# PF_Dolly_Shield4.net
KiCad netlist of a schematic drawn in EAGLE
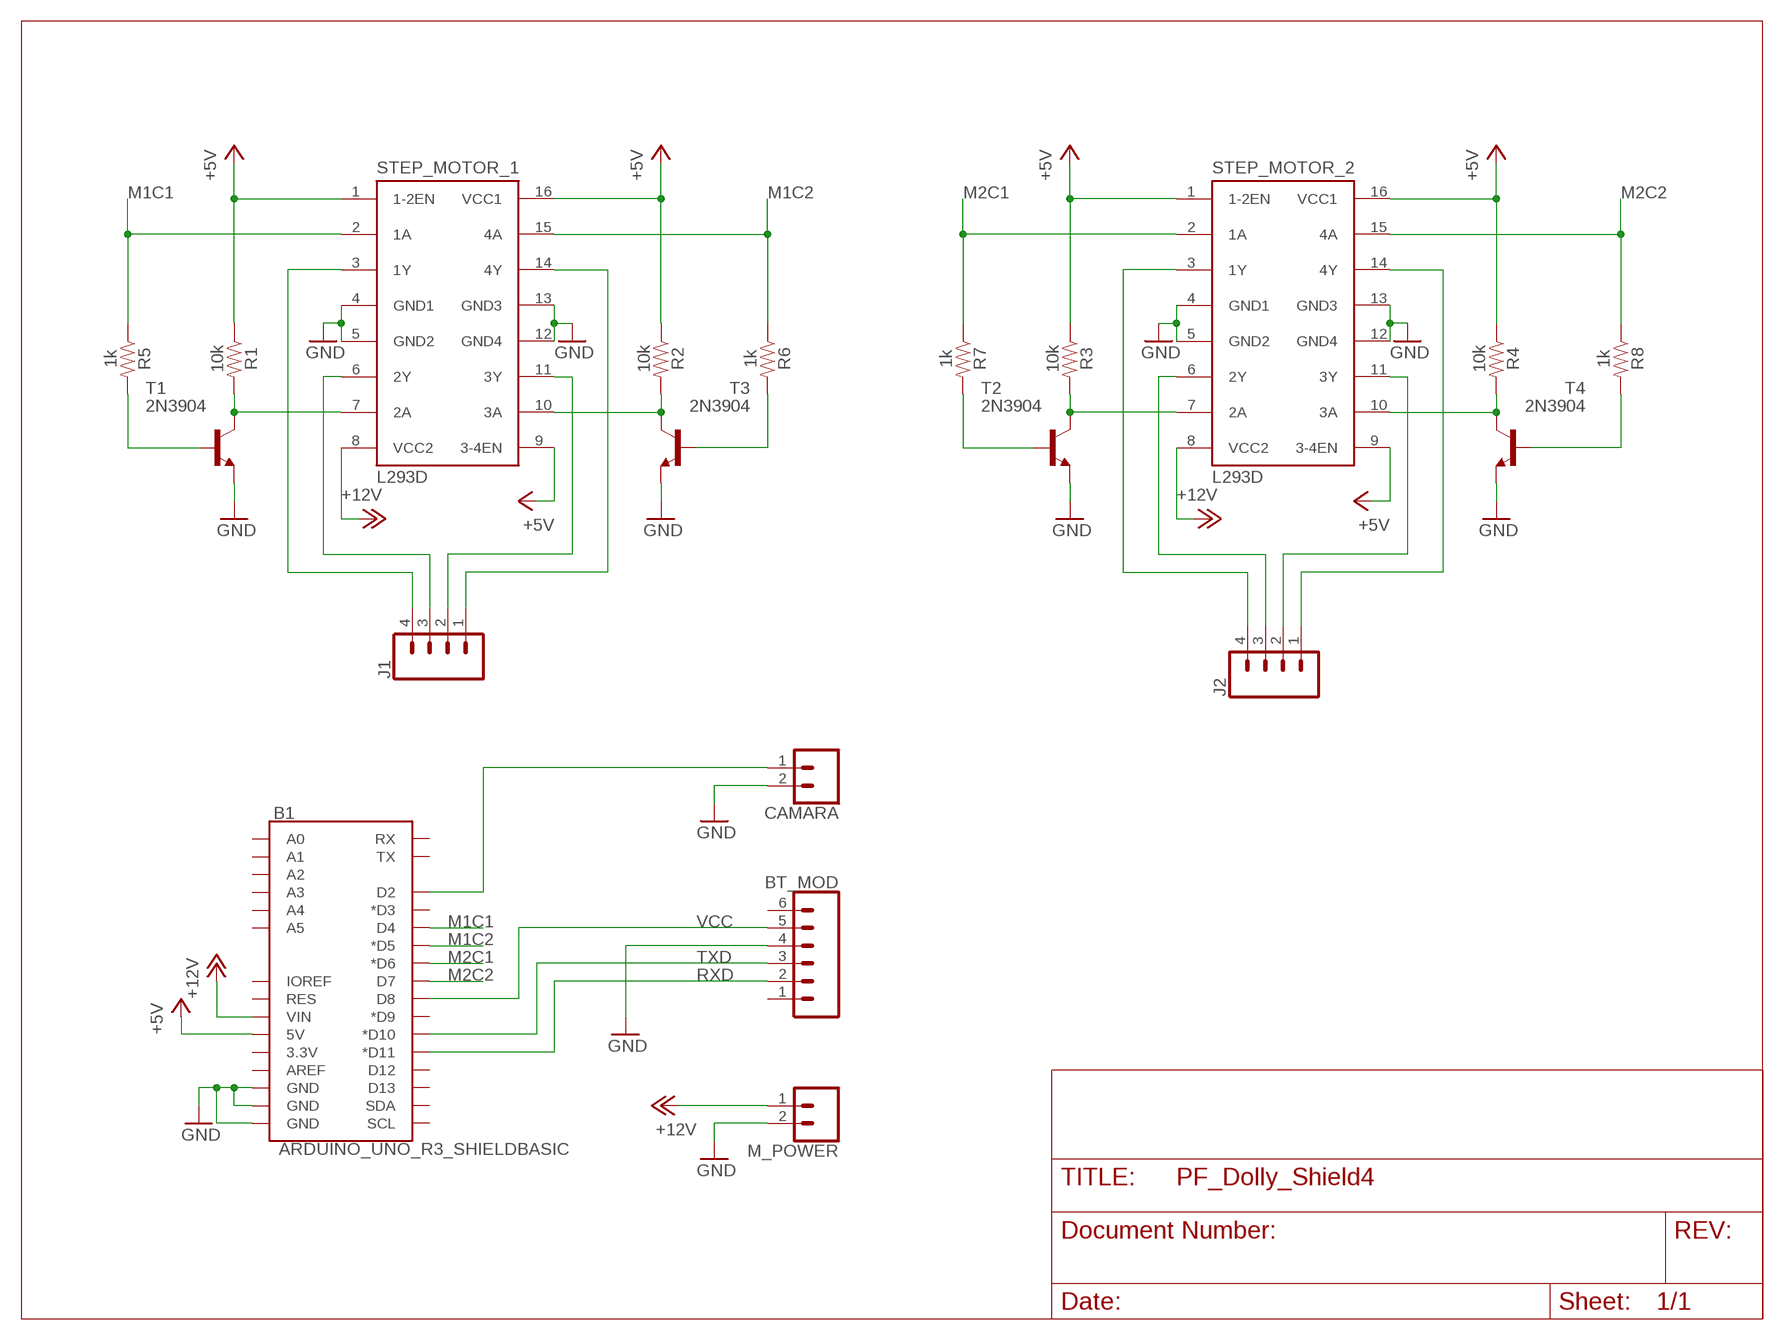
[diagram p0: schematic, sheet 1]

(export (version "E")
  (design (tool "Eeschema 10.0.6"))
  (components
    (comp (ref "B1")
      (value "ARDUINO_UNO_R3_SHIELDBASIC")
      (footprint "eagle-import:UNO_R3_SHIELD")
      (libsource (lib "eagle-import") (part "ARDUINO_UNO_R3_SHIELDBASIC"))
    )
    (comp (ref "BT_MOD")
      (value "CONN_06LONGPADS")
      (footprint "eagle-import:1X06_LONGPADS")
      (libsource (lib "eagle-import") (part "CONN_06LONGPADS"))
    )
    (comp (ref "CAMARA")
      (value "CONN_025MM")
      (footprint "eagle-import:SCREWTERMINAL-5MM-2")
      (libsource (lib "eagle-import") (part "CONN_025MM"))
    )
    (comp (ref "J1")
      (value "CONN_04POLAR")
      (footprint "eagle-import:MOLEX-1X4")
      (libsource (lib "eagle-import") (part "CONN_04POLAR"))
    )
    (comp (ref "J2")
      (value "CONN_04POLAR")
      (footprint "eagle-import:MOLEX-1X4")
      (libsource (lib "eagle-import") (part "CONN_04POLAR"))
    )
    (comp (ref "M_POWER")
      (value "CONN_025MM")
      (footprint "eagle-import:SCREWTERMINAL-5MM-2")
      (libsource (lib "eagle-import") (part "CONN_025MM"))
    )
    (comp (ref "R1")
      (value "10k")
      (footprint "eagle-import:AXIAL-0.3")
      (libsource (lib "eagle-import") (part "10KOHM-HORIZ-1/4W-5%"))
    )
    (comp (ref "R2")
      (value "10k")
      (footprint "eagle-import:AXIAL-0.3")
      (libsource (lib "eagle-import") (part "10KOHM-HORIZ-1/4W-5%"))
    )
    (comp (ref "R3")
      (value "10k")
      (footprint "eagle-import:AXIAL-0.3")
      (libsource (lib "eagle-import") (part "10KOHM-HORIZ-1/4W-5%"))
    )
    (comp (ref "R4")
      (value "10k")
      (footprint "eagle-import:AXIAL-0.3")
      (libsource (lib "eagle-import") (part "10KOHM-HORIZ-1/4W-5%"))
    )
    (comp (ref "R5")
      (value "1k")
      (footprint "eagle-import:AXIAL-0.3")
      (libsource (lib "eagle-import") (part "1KOHM-HORIZ-1/4W-5%"))
    )
    (comp (ref "R6")
      (value "1k")
      (footprint "eagle-import:AXIAL-0.3")
      (libsource (lib "eagle-import") (part "1KOHM-HORIZ-1/4W-5%"))
    )
    (comp (ref "R7")
      (value "1k")
      (footprint "eagle-import:AXIAL-0.3")
      (libsource (lib "eagle-import") (part "1KOHM-HORIZ-1/4W-5%"))
    )
    (comp (ref "R8")
      (value "1k")
      (footprint "eagle-import:AXIAL-0.3")
      (libsource (lib "eagle-import") (part "1KOHM-HORIZ-1/4W-5%"))
    )
    (comp (ref "STEP_MOTOR_1")
      (value "L293D")
      (footprint "eagle-import:DIL16")
      (libsource (lib "eagle-import") (part "L293D"))
    )
    (comp (ref "STEP_MOTOR_2")
      (value "L293D")
      (footprint "eagle-import:DIL16")
      (libsource (lib "eagle-import") (part "L293D"))
    )
    (comp (ref "T1")
      (value "2N3904")
      (footprint "eagle-import:TO92")
      (libsource (lib "eagle-import") (part "2N3904"))
    )
    (comp (ref "T2")
      (value "2N3904")
      (footprint "eagle-import:TO92")
      (libsource (lib "eagle-import") (part "2N3904"))
    )
    (comp (ref "T3")
      (value "2N3904")
      (footprint "eagle-import:TO92")
      (libsource (lib "eagle-import") (part "2N3904"))
    )
    (comp (ref "T4")
      (value "2N3904")
      (footprint "eagle-import:TO92")
      (libsource (lib "eagle-import") (part "2N3904"))
    )
  )
  (nets
    (net (code "1") (name "+5V") (class "Default")
      (node (ref "B1") (pin "5V") (pinfunction "5V_5V") (pintype "bidirectional"))
      (node (ref "R1") (pin "P$1") (pinfunction "1_P$1") (pintype "passive"))
      (node (ref "R2") (pin "P$1") (pinfunction "1_P$1") (pintype "passive"))
      (node (ref "R3") (pin "P$1") (pinfunction "1_P$1") (pintype "passive"))
      (node (ref "R4") (pin "P$1") (pinfunction "1_P$1") (pintype "passive"))
      (node (ref "STEP_MOTOR_1") (pin "1") (pinfunction "1-2EN_1") (pintype "input"))
      (node (ref "STEP_MOTOR_1") (pin "16") (pinfunction "VCC1_16") (pintype "power_in"))
      (node (ref "STEP_MOTOR_1") (pin "9") (pinfunction "3-4EN_9") (pintype "input"))
      (node (ref "STEP_MOTOR_2") (pin "1") (pinfunction "1-2EN_1") (pintype "input"))
      (node (ref "STEP_MOTOR_2") (pin "16") (pinfunction "VCC1_16") (pintype "power_in"))
      (node (ref "STEP_MOTOR_2") (pin "9") (pinfunction "3-4EN_9") (pintype "input"))
    )
    (net (code "2") (name "+12V") (class "Default")
      (node (ref "B1") (pin "VIN") (pinfunction "VIN_VIN") (pintype "bidirectional"))
      (node (ref "M_POWER") (pin "1") (pinfunction "1_1") (pintype "passive"))
      (node (ref "STEP_MOTOR_1") (pin "8") (pinfunction "VCC2_8") (pintype "power_in"))
      (node (ref "STEP_MOTOR_2") (pin "8") (pinfunction "VCC2_8") (pintype "power_in"))
    )
    (net (code "3") (name "/M1C1") (class "Default")
      (node (ref "B1") (pin "D4") (pinfunction "D4_D4") (pintype "bidirectional"))
      (node (ref "R5") (pin "P$1") (pinfunction "1_P$1") (pintype "passive"))
      (node (ref "STEP_MOTOR_1") (pin "2") (pinfunction "1A_2") (pintype "input"))
    )
    (net (code "4") (name "/M1C2") (class "Default")
      (node (ref "B1") (pin "D5") (pinfunction "*D5_D5") (pintype "bidirectional"))
      (node (ref "R6") (pin "P$1") (pinfunction "1_P$1") (pintype "passive"))
      (node (ref "STEP_MOTOR_1") (pin "15") (pinfunction "4A_15") (pintype "input"))
    )
    (net (code "5") (name "/M2C1") (class "Default")
      (node (ref "B1") (pin "D6") (pinfunction "*D6_D6") (pintype "bidirectional"))
      (node (ref "R7") (pin "P$1") (pinfunction "1_P$1") (pintype "passive"))
      (node (ref "STEP_MOTOR_2") (pin "2") (pinfunction "1A_2") (pintype "input"))
    )
    (net (code "6") (name "/M2C2") (class "Default")
      (node (ref "B1") (pin "D7") (pinfunction "D7_D7") (pintype "bidirectional"))
      (node (ref "R8") (pin "P$1") (pinfunction "1_P$1") (pintype "passive"))
      (node (ref "STEP_MOTOR_2") (pin "15") (pinfunction "4A_15") (pintype "input"))
    )
    (net (code "7") (name "/RXD") (class "Default")
      (node (ref "B1") (pin "D11") (pinfunction "*D11_D11") (pintype "bidirectional"))
      (node (ref "BT_MOD") (pin "2") (pinfunction "2_2") (pintype "passive"))
    )
    (net (code "8") (name "/TXD") (class "Default")
      (node (ref "B1") (pin "D10") (pinfunction "*D10_D10") (pintype "bidirectional"))
      (node (ref "BT_MOD") (pin "3") (pinfunction "3_3") (pintype "passive"))
    )
    (net (code "9") (name "/VCC") (class "Default")
      (node (ref "B1") (pin "D8") (pinfunction "D8_D8") (pintype "bidirectional"))
      (node (ref "BT_MOD") (pin "5") (pinfunction "5_5") (pintype "passive"))
    )
    (net (code "10") (name "GND") (class "Default")
      (node (ref "B1") (pin "GND@0") (pinfunction "GND_GND@0") (pintype "bidirectional"))
      (node (ref "B1") (pin "GND@1") (pinfunction "GND_GND@1") (pintype "bidirectional"))
      (node (ref "B1") (pin "GND@2") (pinfunction "GND_GND@2") (pintype "bidirectional"))
      (node (ref "BT_MOD") (pin "4") (pinfunction "4_4") (pintype "passive"))
      (node (ref "CAMARA") (pin "2") (pinfunction "2_2") (pintype "passive"))
      (node (ref "M_POWER") (pin "2") (pinfunction "2_2") (pintype "passive"))
      (node (ref "STEP_MOTOR_1") (pin "12") (pinfunction "GND4_12") (pintype "power_in"))
      (node (ref "STEP_MOTOR_1") (pin "13") (pinfunction "GND3_13") (pintype "power_in"))
      (node (ref "STEP_MOTOR_1") (pin "4") (pinfunction "GND1_4") (pintype "power_in"))
      (node (ref "STEP_MOTOR_1") (pin "5") (pinfunction "GND2_5") (pintype "power_in"))
      (node (ref "STEP_MOTOR_2") (pin "12") (pinfunction "GND4_12") (pintype "power_in"))
      (node (ref "STEP_MOTOR_2") (pin "13") (pinfunction "GND3_13") (pintype "power_in"))
      (node (ref "STEP_MOTOR_2") (pin "4") (pinfunction "GND1_4") (pintype "power_in"))
      (node (ref "STEP_MOTOR_2") (pin "5") (pinfunction "GND2_5") (pintype "power_in"))
      (node (ref "T1") (pin "3") (pinfunction "E_3") (pintype "passive"))
      (node (ref "T2") (pin "3") (pinfunction "E_3") (pintype "passive"))
      (node (ref "T3") (pin "3") (pinfunction "E_3") (pintype "passive"))
      (node (ref "T4") (pin "3") (pinfunction "E_3") (pintype "passive"))
    )
    (net (code "11") (name "Net-(B1-PadD2)") (class "Default")
      (node (ref "B1") (pin "D2") (pinfunction "D2_D2") (pintype "bidirectional"))
      (node (ref "CAMARA") (pin "1") (pinfunction "1_1") (pintype "passive"))
    )
    (net (code "12") (name "Net-(R1-2)") (class "Default")
      (node (ref "R1") (pin "P$2") (pinfunction "2_P$2") (pintype "passive"))
      (node (ref "STEP_MOTOR_1") (pin "7") (pinfunction "2A_7") (pintype "input"))
      (node (ref "T1") (pin "1") (pinfunction "C_1") (pintype "passive"))
    )
    (net (code "13") (name "Net-(R2-2)") (class "Default")
      (node (ref "R2") (pin "P$2") (pinfunction "2_P$2") (pintype "passive"))
      (node (ref "STEP_MOTOR_1") (pin "10") (pinfunction "3A_10") (pintype "input"))
      (node (ref "T3") (pin "1") (pinfunction "C_1") (pintype "passive"))
    )
    (net (code "14") (name "Net-(R3-2)") (class "Default")
      (node (ref "R3") (pin "P$2") (pinfunction "2_P$2") (pintype "passive"))
      (node (ref "STEP_MOTOR_2") (pin "7") (pinfunction "2A_7") (pintype "input"))
      (node (ref "T2") (pin "1") (pinfunction "C_1") (pintype "passive"))
    )
    (net (code "15") (name "Net-(R4-2)") (class "Default")
      (node (ref "R4") (pin "P$2") (pinfunction "2_P$2") (pintype "passive"))
      (node (ref "STEP_MOTOR_2") (pin "10") (pinfunction "3A_10") (pintype "input"))
      (node (ref "T4") (pin "1") (pinfunction "C_1") (pintype "passive"))
    )
    (net (code "16") (name "Net-(R5-2)") (class "Default")
      (node (ref "R5") (pin "P$2") (pinfunction "2_P$2") (pintype "passive"))
      (node (ref "T1") (pin "2") (pinfunction "B_2") (pintype "passive"))
    )
    (net (code "17") (name "Net-(R6-2)") (class "Default")
      (node (ref "R6") (pin "P$2") (pinfunction "2_P$2") (pintype "passive"))
      (node (ref "T3") (pin "2") (pinfunction "B_2") (pintype "passive"))
    )
    (net (code "18") (name "Net-(R7-2)") (class "Default")
      (node (ref "R7") (pin "P$2") (pinfunction "2_P$2") (pintype "passive"))
      (node (ref "T2") (pin "2") (pinfunction "B_2") (pintype "passive"))
    )
    (net (code "19") (name "Net-(R8-2)") (class "Default")
      (node (ref "R8") (pin "P$2") (pinfunction "2_P$2") (pintype "passive"))
      (node (ref "T4") (pin "2") (pinfunction "B_2") (pintype "passive"))
    )
    (net (code "20") (name "Net-(STEP_MOTOR_1-1Y)") (class "Default")
      (node (ref "J1") (pin "4") (pinfunction "4_4") (pintype "passive"))
      (node (ref "STEP_MOTOR_1") (pin "3") (pinfunction "1Y_3") (pintype "output"))
    )
    (net (code "21") (name "Net-(STEP_MOTOR_1-2Y)") (class "Default")
      (node (ref "J1") (pin "3") (pinfunction "3_3") (pintype "passive"))
      (node (ref "STEP_MOTOR_1") (pin "6") (pinfunction "2Y_6") (pintype "output"))
    )
    (net (code "22") (name "Net-(STEP_MOTOR_1-3Y)") (class "Default")
      (node (ref "J1") (pin "2") (pinfunction "2_2") (pintype "passive"))
      (node (ref "STEP_MOTOR_1") (pin "11") (pinfunction "3Y_11") (pintype "output"))
    )
    (net (code "23") (name "Net-(STEP_MOTOR_1-4Y)") (class "Default")
      (node (ref "J1") (pin "1") (pinfunction "1_1") (pintype "passive"))
      (node (ref "STEP_MOTOR_1") (pin "14") (pinfunction "4Y_14") (pintype "output"))
    )
    (net (code "24") (name "Net-(STEP_MOTOR_2-1Y)") (class "Default")
      (node (ref "J2") (pin "4") (pinfunction "4_4") (pintype "passive"))
      (node (ref "STEP_MOTOR_2") (pin "3") (pinfunction "1Y_3") (pintype "output"))
    )
    (net (code "25") (name "Net-(STEP_MOTOR_2-2Y)") (class "Default")
      (node (ref "J2") (pin "3") (pinfunction "3_3") (pintype "passive"))
      (node (ref "STEP_MOTOR_2") (pin "6") (pinfunction "2Y_6") (pintype "output"))
    )
    (net (code "26") (name "Net-(STEP_MOTOR_2-3Y)") (class "Default")
      (node (ref "J2") (pin "2") (pinfunction "2_2") (pintype "passive"))
      (node (ref "STEP_MOTOR_2") (pin "11") (pinfunction "3Y_11") (pintype "output"))
    )
    (net (code "27") (name "Net-(STEP_MOTOR_2-4Y)") (class "Default")
      (node (ref "J2") (pin "1") (pinfunction "1_1") (pintype "passive"))
      (node (ref "STEP_MOTOR_2") (pin "14") (pinfunction "4Y_14") (pintype "output"))
    )
    (net (code "28") (name "unconnected-(B1-*D3-PadD3)") (class "Default")
      (node (ref "B1") (pin "D3") (pinfunction "*D3_D3") (pintype "bidirectional"))
    )
    (net (code "29") (name "unconnected-(B1-*D9-PadD9)") (class "Default")
      (node (ref "B1") (pin "D9") (pinfunction "*D9_D9") (pintype "bidirectional"))
    )
    (net (code "30") (name "unconnected-(B1-Pad3.3V)") (class "Default")
      (node (ref "B1") (pin "3.3V") (pinfunction "3.3V_3.3V") (pintype "bidirectional"))
    )
    (net (code "31") (name "unconnected-(B1-PadA0)") (class "Default")
      (node (ref "B1") (pin "A0") (pinfunction "A0_A0") (pintype "bidirectional"))
    )
    (net (code "32") (name "unconnected-(B1-PadA1)") (class "Default")
      (node (ref "B1") (pin "A1") (pinfunction "A1_A1") (pintype "bidirectional"))
    )
    (net (code "33") (name "unconnected-(B1-PadA2)") (class "Default")
      (node (ref "B1") (pin "A2") (pinfunction "A2_A2") (pintype "bidirectional"))
    )
    (net (code "34") (name "unconnected-(B1-PadA3)") (class "Default")
      (node (ref "B1") (pin "A3") (pinfunction "A3_A3") (pintype "bidirectional"))
    )
    (net (code "35") (name "unconnected-(B1-PadA4)") (class "Default")
      (node (ref "B1") (pin "A4") (pinfunction "A4_A4") (pintype "bidirectional"))
    )
    (net (code "36") (name "unconnected-(B1-PadA5)") (class "Default")
      (node (ref "B1") (pin "A5") (pinfunction "A5_A5") (pintype "bidirectional"))
    )
    (net (code "37") (name "unconnected-(B1-PadAREF)") (class "Default")
      (node (ref "B1") (pin "AREF") (pinfunction "AREF_AREF") (pintype "bidirectional"))
    )
    (net (code "38") (name "unconnected-(B1-PadD12)") (class "Default")
      (node (ref "B1") (pin "D12") (pinfunction "D12_D12") (pintype "bidirectional"))
    )
    (net (code "39") (name "unconnected-(B1-PadD13)") (class "Default")
      (node (ref "B1") (pin "D13") (pinfunction "D13_D13") (pintype "bidirectional"))
    )
    (net (code "40") (name "unconnected-(B1-PadIOREF)") (class "Default")
      (node (ref "B1") (pin "IOREF") (pinfunction "IOREF_IOREF") (pintype "bidirectional"))
    )
    (net (code "41") (name "unconnected-(B1-PadRES)") (class "Default")
      (node (ref "B1") (pin "RES") (pinfunction "RES_RES") (pintype "bidirectional"))
    )
    (net (code "42") (name "unconnected-(B1-PadRX)") (class "Default")
      (node (ref "B1") (pin "RX") (pinfunction "RX_RX") (pintype "bidirectional"))
    )
    (net (code "43") (name "unconnected-(B1-PadSCL)") (class "Default")
      (node (ref "B1") (pin "SCL") (pinfunction "SCL_SCL") (pintype "bidirectional"))
    )
    (net (code "44") (name "unconnected-(B1-PadSDA)") (class "Default")
      (node (ref "B1") (pin "SDA") (pinfunction "SDA_SDA") (pintype "bidirectional"))
    )
    (net (code "45") (name "unconnected-(B1-PadTX)") (class "Default")
      (node (ref "B1") (pin "TX") (pinfunction "TX_TX") (pintype "bidirectional"))
    )
    (net (code "46") (name "unconnected-(BT_MOD-Pad1)") (class "Default")
      (node (ref "BT_MOD") (pin "1") (pinfunction "1_1") (pintype "passive"))
    )
    (net (code "47") (name "unconnected-(BT_MOD-Pad6)") (class "Default")
      (node (ref "BT_MOD") (pin "6") (pinfunction "6_6") (pintype "passive"))
    )
  )
)
